# W034X.net
KiCad netlist of a schematic drawn in EAGLE
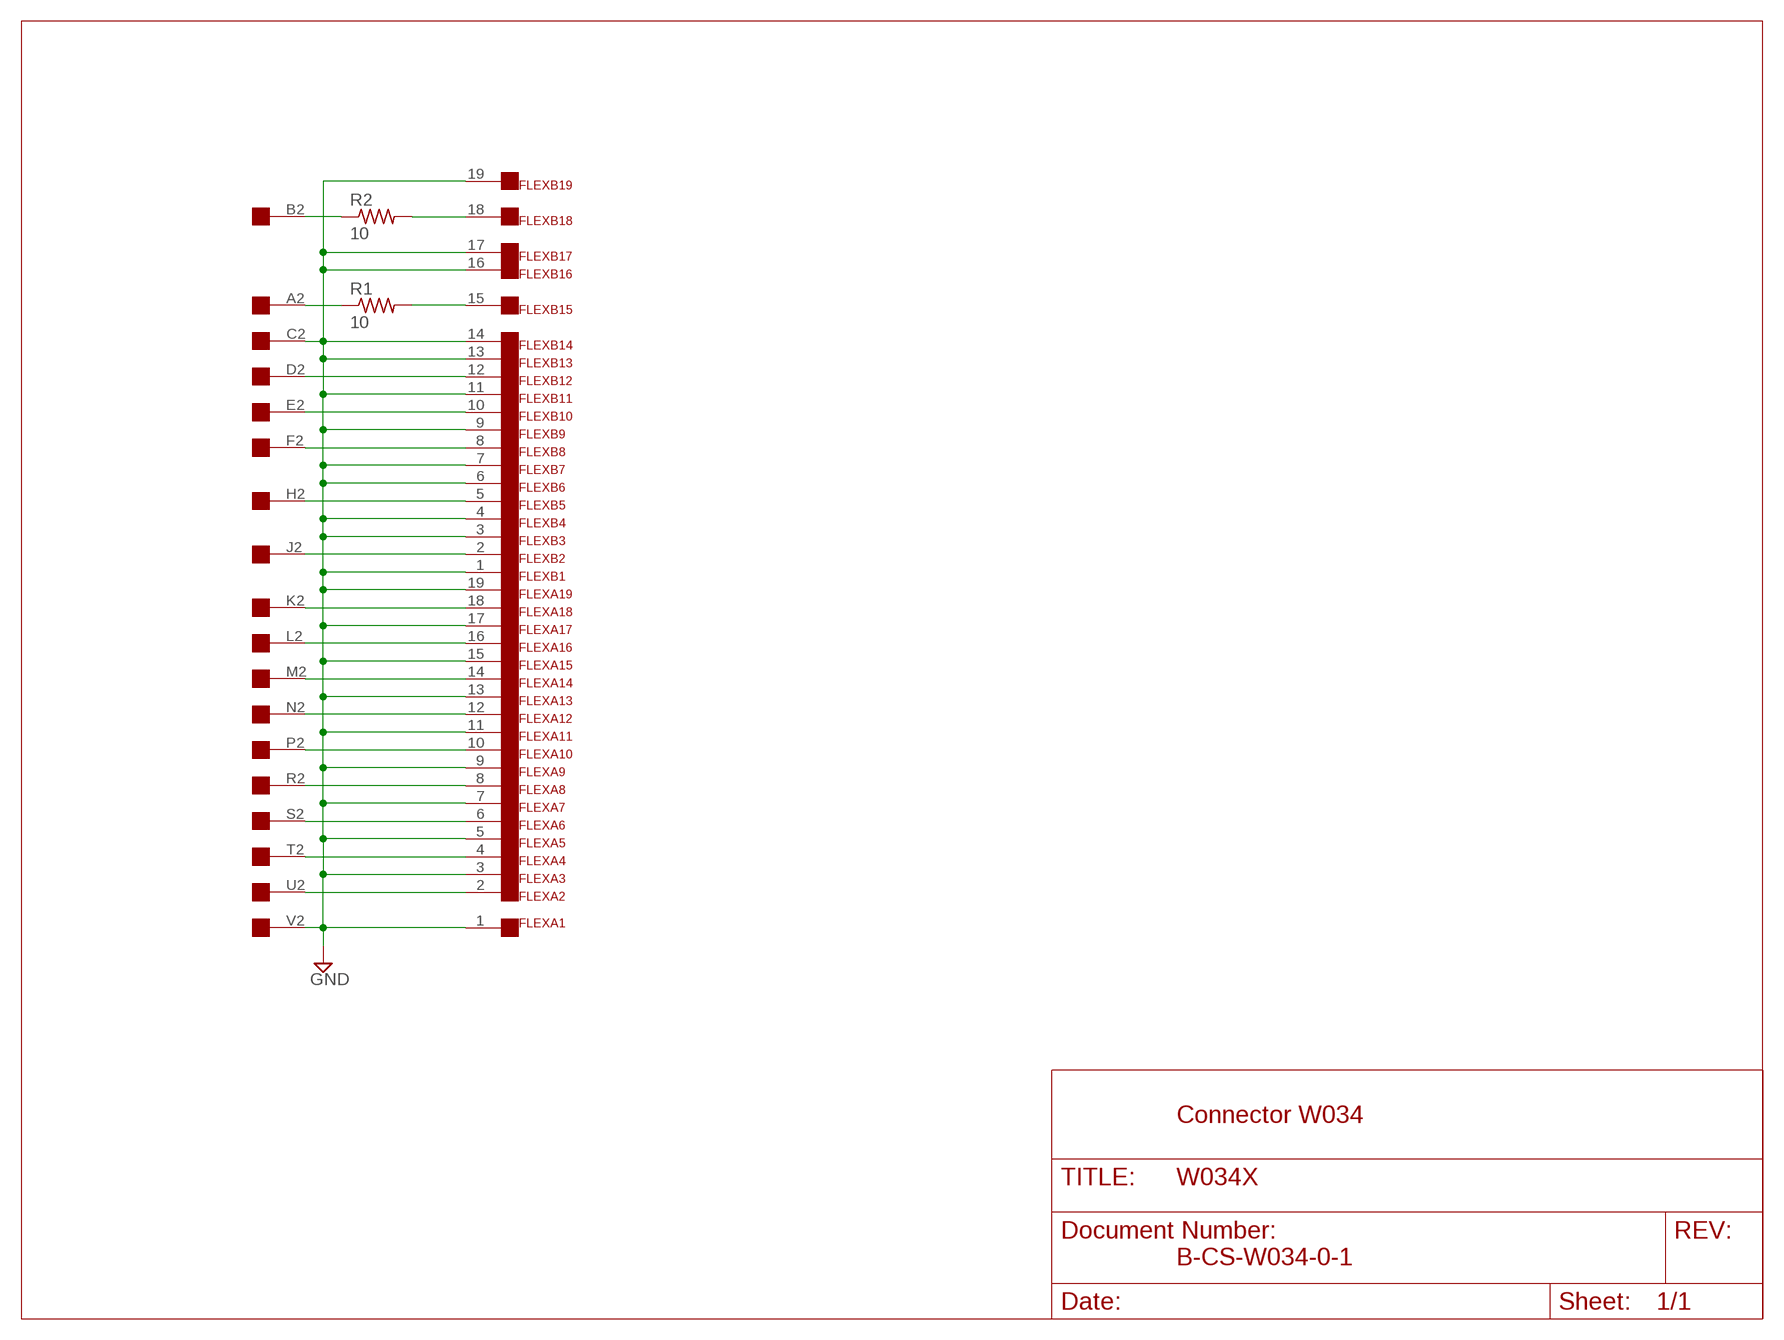
[diagram p0: schematic, sheet 1]

(export (version "E")
  (design (tool "Eeschema 10.0.6"))
  (components
    (comp (ref "FLEXA")
      (value "FLEX19")
      (footprint "eagle-import:FLEX19")
      (libsource (lib "eagle-import") (part "FLEX19"))
    )
    (comp (ref "FLEXB")
      (value "FLEX19")
      (footprint "eagle-import:FLEX19")
      (libsource (lib "eagle-import") (part "FLEX19"))
    )
    (comp (ref "R1")
      (value "10")
      (footprint "eagle-import:0207_10")
      (libsource (lib "eagle-import") (part "R-US_0207/10"))
    )
    (comp (ref "R2")
      (value "10")
      (footprint "eagle-import:0207_10")
      (libsource (lib "eagle-import") (part "R-US_0207/10"))
    )
    (comp (ref "U$2")
      (value "EDGE-1")
      (footprint "eagle-import:EDGE-CON1")
      (libsource (lib "eagle-import") (part "EDGE-1"))
    )
  )
  (nets
    (net (code "1") (name "GND") (class "Default")
      (node (ref "FLEXA") (pin "1") (pinfunction "1_1") (pintype "passive"))
      (node (ref "FLEXA") (pin "11") (pinfunction "1_11") (pintype "passive"))
      (node (ref "FLEXA") (pin "13") (pinfunction "1_13") (pintype "passive"))
      (node (ref "FLEXA") (pin "15") (pinfunction "1_15") (pintype "passive"))
      (node (ref "FLEXA") (pin "17") (pinfunction "1_17") (pintype "passive"))
      (node (ref "FLEXA") (pin "19") (pinfunction "1_19") (pintype "passive"))
      (node (ref "FLEXA") (pin "3") (pinfunction "1_3") (pintype "passive"))
      (node (ref "FLEXA") (pin "5") (pinfunction "1_5") (pintype "passive"))
      (node (ref "FLEXA") (pin "7") (pinfunction "1_7") (pintype "passive"))
      (node (ref "FLEXA") (pin "9") (pinfunction "1_9") (pintype "passive"))
      (node (ref "FLEXB") (pin "1") (pinfunction "1_1") (pintype "passive"))
      (node (ref "FLEXB") (pin "11") (pinfunction "1_11") (pintype "passive"))
      (node (ref "FLEXB") (pin "13") (pinfunction "1_13") (pintype "passive"))
      (node (ref "FLEXB") (pin "14") (pinfunction "1_14") (pintype "passive"))
      (node (ref "FLEXB") (pin "16") (pinfunction "1_16") (pintype "passive"))
      (node (ref "FLEXB") (pin "17") (pinfunction "1_17") (pintype "passive"))
      (node (ref "FLEXB") (pin "19") (pinfunction "1_19") (pintype "passive"))
      (node (ref "FLEXB") (pin "3") (pinfunction "1_3") (pintype "passive"))
      (node (ref "FLEXB") (pin "4") (pinfunction "1_4") (pintype "passive"))
      (node (ref "FLEXB") (pin "6") (pinfunction "1_6") (pintype "passive"))
      (node (ref "FLEXB") (pin "7") (pinfunction "1_7") (pintype "passive"))
      (node (ref "FLEXB") (pin "9") (pinfunction "1_9") (pintype "passive"))
      (node (ref "U$2") (pin "C2") (pinfunction "1_C2") (pintype "bidirectional"))
      (node (ref "U$2") (pin "V2") (pinfunction "1_V2") (pintype "bidirectional"))
    )
    (net (code "2") (name "Net-(FLEXAB-1)") (class "Default")
      (node (ref "FLEXA") (pin "10") (pinfunction "1_10") (pintype "passive"))
      (node (ref "U$2") (pin "P2") (pinfunction "1_P2") (pintype "bidirectional"))
    )
    (net (code "3") (name "Net-(FLEXAD-1)") (class "Default")
      (node (ref "FLEXA") (pin "12") (pinfunction "1_12") (pintype "passive"))
      (node (ref "U$2") (pin "N2") (pinfunction "1_N2") (pintype "bidirectional"))
    )
    (net (code "4") (name "Net-(FLEXAF-1)") (class "Default")
      (node (ref "FLEXA") (pin "14") (pinfunction "1_14") (pintype "passive"))
      (node (ref "U$2") (pin "M2") (pinfunction "1_M2") (pintype "bidirectional"))
    )
    (net (code "5") (name "Net-(FLEXAH-1)") (class "Default")
      (node (ref "FLEXA") (pin "16") (pinfunction "1_16") (pintype "passive"))
      (node (ref "U$2") (pin "L2") (pinfunction "1_L2") (pintype "bidirectional"))
    )
    (net (code "6") (name "Net-(FLEXAJ-1)") (class "Default")
      (node (ref "FLEXA") (pin "18") (pinfunction "1_18") (pintype "passive"))
      (node (ref "U$2") (pin "K2") (pinfunction "1_K2") (pintype "bidirectional"))
    )
    (net (code "7") (name "Net-(FLEXAL-1)") (class "Default")
      (node (ref "FLEXA") (pin "2") (pinfunction "1_2") (pintype "passive"))
      (node (ref "U$2") (pin "U2") (pinfunction "1_U2") (pintype "bidirectional"))
    )
    (net (code "8") (name "Net-(FLEXAN-1)") (class "Default")
      (node (ref "FLEXA") (pin "4") (pinfunction "1_4") (pintype "passive"))
      (node (ref "U$2") (pin "T2") (pinfunction "1_T2") (pintype "bidirectional"))
    )
    (net (code "9") (name "Net-(FLEXAP-1)") (class "Default")
      (node (ref "FLEXA") (pin "6") (pinfunction "1_6") (pintype "passive"))
      (node (ref "U$2") (pin "S2") (pinfunction "1_S2") (pintype "bidirectional"))
    )
    (net (code "10") (name "Net-(FLEXAR-1)") (class "Default")
      (node (ref "FLEXA") (pin "8") (pinfunction "1_8") (pintype "passive"))
      (node (ref "U$2") (pin "R2") (pinfunction "1_R2") (pintype "bidirectional"))
    )
    (net (code "11") (name "Net-(FLEXBB-1)") (class "Default")
      (node (ref "FLEXB") (pin "10") (pinfunction "1_10") (pintype "passive"))
      (node (ref "U$2") (pin "E2") (pinfunction "1_E2") (pintype "bidirectional"))
    )
    (net (code "12") (name "Net-(FLEXBD-1)") (class "Default")
      (node (ref "FLEXB") (pin "12") (pinfunction "1_12") (pintype "passive"))
      (node (ref "U$2") (pin "D2") (pinfunction "1_D2") (pintype "bidirectional"))
    )
    (net (code "13") (name "Net-(FLEXBG-1)") (class "Default")
      (node (ref "FLEXB") (pin "15") (pinfunction "1_15") (pintype "passive"))
      (node (ref "R1") (pin "2") (pinfunction "2_2") (pintype "passive"))
    )
    (net (code "14") (name "Net-(FLEXBJ-1)") (class "Default")
      (node (ref "FLEXB") (pin "18") (pinfunction "1_18") (pintype "passive"))
      (node (ref "R2") (pin "2") (pinfunction "2_2") (pintype "passive"))
    )
    (net (code "15") (name "Net-(FLEXBL-1)") (class "Default")
      (node (ref "FLEXB") (pin "2") (pinfunction "1_2") (pintype "passive"))
      (node (ref "U$2") (pin "J2") (pinfunction "1_J2") (pintype "bidirectional"))
    )
    (net (code "16") (name "Net-(FLEXBO-1)") (class "Default")
      (node (ref "FLEXB") (pin "5") (pinfunction "1_5") (pintype "passive"))
      (node (ref "U$2") (pin "H2") (pinfunction "1_H2") (pintype "bidirectional"))
    )
    (net (code "17") (name "Net-(FLEXBR-1)") (class "Default")
      (node (ref "FLEXB") (pin "8") (pinfunction "1_8") (pintype "passive"))
      (node (ref "U$2") (pin "F2") (pinfunction "1_F2") (pintype "bidirectional"))
    )
    (net (code "18") (name "Net-(U$2A-1)") (class "Default")
      (node (ref "R1") (pin "1") (pinfunction "1_1") (pintype "passive"))
      (node (ref "U$2") (pin "A2") (pinfunction "1_A2") (pintype "bidirectional"))
    )
    (net (code "19") (name "Net-(U$2B-1)") (class "Default")
      (node (ref "R2") (pin "1") (pinfunction "1_1") (pintype "passive"))
      (node (ref "U$2") (pin "B2") (pinfunction "1_B2") (pintype "bidirectional"))
    )
  )
)
